# Clock_circuit.net
KiCad netlist of a schematic drawn in Altium Designer
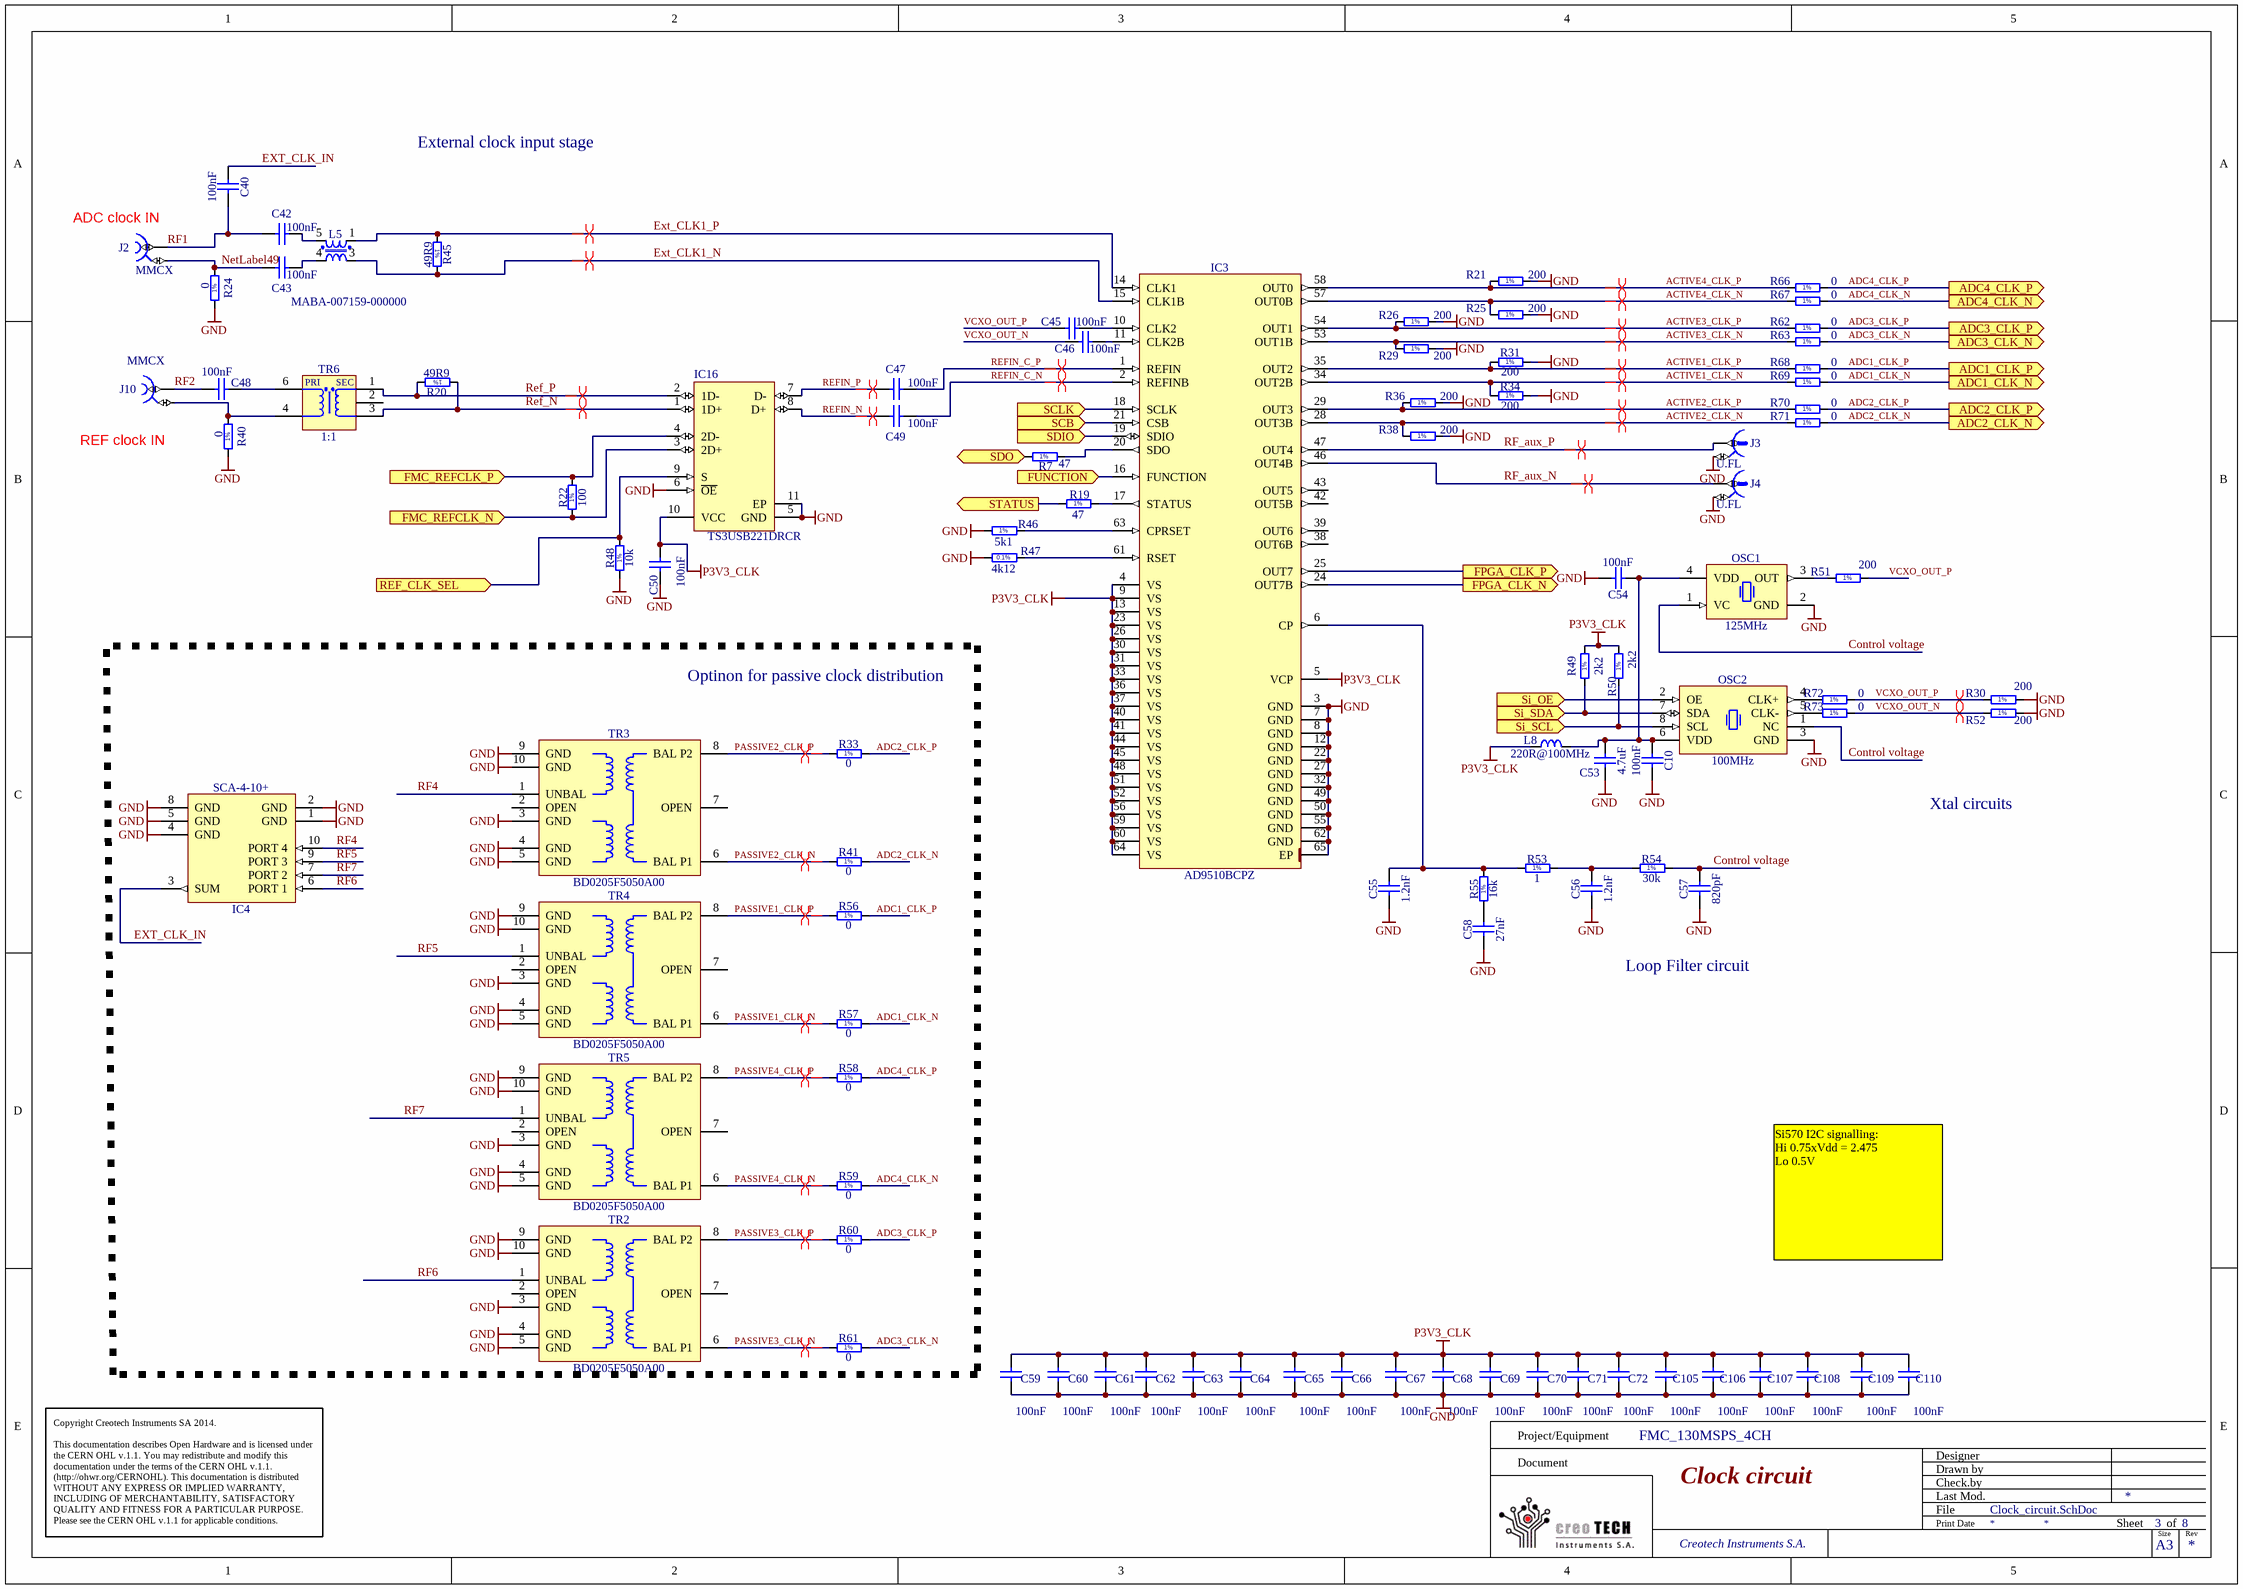
[diagram p0: Clock_circuit.SchDoc]

(export (version "E")
  (design (tool "Eeschema 10.0.6"))
  (components
    (comp (ref "C10")
      (value "100nF")
      (footprint "CAPC0603X33N")
      (description "Non-polarised capacitor")
      (fields
        (field (name "PART NUMBER") "CC0201_100NF_6.3V_10%_X5R")
        (field (name "VOLTAGE") "6.3V")
        (field (name "AUTHOR") "CERN DEM JLC")
      )
      (libsource (lib "Capacitors") (part "Capacitor - non polarized"))
    )
    (comp (ref "C40")
      (value "100nF")
      (footprint "CAPC0603X33N")
      (description "Non-polarised capacitor")
      (fields
        (field (name "PART NUMBER") "CC0201_100NF_6.3V_10%_X5R")
        (field (name "VOLTAGE") "6.3V")
        (field (name "AUTHOR") "CERN DEM JLC")
      )
      (libsource (lib "Capacitors") (part "Capacitor - non polarized"))
    )
    (comp (ref "C42")
      (value "100nF")
      (footprint "CAPC0603X33N")
      (description "Non-polarised capacitor")
      (fields
        (field (name "PART NUMBER") "CC0201_100NF_6.3V_10%_X5R")
        (field (name "VOLTAGE") "6.3V")
        (field (name "AUTHOR") "CERN DEM JLC")
      )
      (libsource (lib "Capacitors") (part "Capacitor - non polarized"))
    )
    (comp (ref "C43")
      (value "100nF")
      (footprint "CAPC0603X33N")
      (description "Non-polarised capacitor")
      (fields
        (field (name "PART NUMBER") "CC0201_100NF_6.3V_10%_X5R")
        (field (name "VOLTAGE") "6.3V")
        (field (name "AUTHOR") "CERN DEM JLC")
      )
      (libsource (lib "Capacitors") (part "Capacitor - non polarized"))
    )
    (comp (ref "C45")
      (value "100nF")
      (footprint "CAPC0603X33N")
      (description "Non-polarised capacitor")
      (fields
        (field (name "PART NUMBER") "CC0201_100NF_6.3V_10%_X5R")
        (field (name "VOLTAGE") "6.3V")
        (field (name "AUTHOR") "CERN DEM JLC")
      )
      (libsource (lib "Capacitors") (part "Capacitor - non polarized"))
    )
    (comp (ref "C46")
      (value "100nF")
      (footprint "CAPC0603X33N")
      (description "Non-polarised capacitor")
      (fields
        (field (name "PART NUMBER") "CC0201_100NF_6.3V_10%_X5R")
        (field (name "VOLTAGE") "6.3V")
        (field (name "AUTHOR") "CERN DEM JLC")
      )
      (libsource (lib "Capacitors") (part "Capacitor - non polarized"))
    )
    (comp (ref "C47")
      (value "100nF")
      (footprint "CAPC0603X33N")
      (description "Non-polarised capacitor")
      (fields
        (field (name "PART NUMBER") "CC0201_100NF_6.3V_10%_X5R")
        (field (name "VOLTAGE") "6.3V")
        (field (name "AUTHOR") "CERN DEM JLC")
      )
      (libsource (lib "Capacitors") (part "Capacitor - non polarized"))
    )
    (comp (ref "C48")
      (value "100nF")
      (footprint "CAPC0603X33N")
      (description "Non-polarised capacitor")
      (fields
        (field (name "PART NUMBER") "CC0201_100NF_6.3V_10%_X5R")
        (field (name "VOLTAGE") "6.3V")
        (field (name "AUTHOR") "CERN DEM JLC")
      )
      (libsource (lib "Capacitors") (part "Capacitor - non polarized"))
    )
    (comp (ref "C49")
      (value "100nF")
      (footprint "CAPC0603X33N")
      (description "Non-polarised capacitor")
      (fields
        (field (name "PART NUMBER") "CC0201_100NF_6.3V_10%_X5R")
        (field (name "VOLTAGE") "6.3V")
        (field (name "AUTHOR") "CERN DEM JLC")
      )
      (libsource (lib "Capacitors") (part "Capacitor - non polarized"))
    )
    (comp (ref "C50")
      (value "100nF")
      (footprint "CAPC0603X33N")
      (description "Non-polarised capacitor")
      (fields
        (field (name "PART NUMBER") "CC0201_100NF_6.3V_10%_X5R")
        (field (name "VOLTAGE") "6.3V")
        (field (name "AUTHOR") "CERN DEM JLC")
      )
      (libsource (lib "Capacitors") (part "Capacitor - non polarized"))
    )
    (comp (ref "C53")
      (value "4.7uF")
      (footprint "CAPC1608X87N")
      (description "Non-polarised capacitor")
      (fields
        (field (name "PART NUMBER") "CC0603_4.7UF_6.3V_10%_X5R")
        (field (name "VOLTAGE") "6.3V")
        (field (name "AUTHOR") "CERN DEM JLC")
      )
      (libsource (lib "Capacitors") (part "Capacitor - non polarized"))
    )
    (comp (ref "C54")
      (value "100nF")
      (footprint "CAPC0603X33N")
      (description "Non-polarised capacitor")
      (fields
        (field (name "PART NUMBER") "CC0201_100NF_6.3V_10%_X5R")
        (field (name "VOLTAGE") "6.3V")
        (field (name "AUTHOR") "CERN DEM JLC")
      )
      (libsource (lib "Capacitors") (part "Capacitor - non polarized"))
    )
    (comp (ref "C55")
      (value "1.2nF")
      (footprint "CAPC1608X87N")
      (description "Non-polarised capacitor")
      (fields
        (field (name "PART NUMBER") "CC0603_1.2NF_50V_10%_X7R")
        (field (name "VOLTAGE") "50V")
        (field (name "AUTHOR") "CERN DEM JLC")
      )
      (libsource (lib "Capacitors") (part "Capacitor - non polarized"))
    )
    (comp (ref "C56")
      (value "1.2nF")
      (footprint "CAPC1608X87N")
      (description "Non-polarised capacitor")
      (fields
        (field (name "PART NUMBER") "CC0603_1.2NF_50V_10%_X7R")
        (field (name "VOLTAGE") "50V")
        (field (name "AUTHOR") "CERN DEM JLC")
      )
      (libsource (lib "Capacitors") (part "Capacitor - non polarized"))
    )
    (comp (ref "C57")
      (value "820pF")
      (footprint "CAPC1608X87N")
      (description "Non-polarised capacitor")
      (fields
        (field (name "PART NUMBER") "CC0603_820PF_50V_10%_X7R")
        (field (name "VOLTAGE") "50V")
        (field (name "AUTHOR") "CERN DEM JLC")
      )
      (libsource (lib "Capacitors") (part "Capacitor - non polarized"))
    )
    (comp (ref "C58")
      (value "27nF")
      (footprint "CAPC1608X87N")
      (description "Non-polarised capacitor")
      (fields
        (field (name "PART NUMBER") "CC0603_27NF_25V_10%_X7R")
        (field (name "VOLTAGE") "25V")
        (field (name "AUTHOR") "CERN DEM JLC")
      )
      (libsource (lib "Capacitors") (part "Capacitor - non polarized"))
    )
    (comp (ref "C59")
      (value "100nF")
      (footprint "CAPC0603X33N")
      (description "Non-polarised capacitor")
      (fields
        (field (name "PART NUMBER") "CC0201_100NF_6.3V_10%_X5R")
        (field (name "VOLTAGE") "6.3V")
        (field (name "AUTHOR") "CERN DEM JLC")
      )
      (libsource (lib "Capacitors") (part "Capacitor - non polarized"))
    )
    (comp (ref "C60")
      (value "100nF")
      (footprint "CAPC0603X33N")
      (description "Non-polarised capacitor")
      (fields
        (field (name "PART NUMBER") "CC0201_100NF_6.3V_10%_X5R")
        (field (name "VOLTAGE") "6.3V")
        (field (name "AUTHOR") "CERN DEM JLC")
      )
      (libsource (lib "Capacitors") (part "Capacitor - non polarized"))
    )
    (comp (ref "C61")
      (value "100nF")
      (footprint "CAPC0603X33N")
      (description "Non-polarised capacitor")
      (fields
        (field (name "PART NUMBER") "CC0201_100NF_6.3V_10%_X5R")
        (field (name "VOLTAGE") "6.3V")
        (field (name "AUTHOR") "CERN DEM JLC")
      )
      (libsource (lib "Capacitors") (part "Capacitor - non polarized"))
    )
    (comp (ref "C62")
      (value "100nF")
      (footprint "CAPC0603X33N")
      (description "Non-polarised capacitor")
      (fields
        (field (name "PART NUMBER") "CC0201_100NF_6.3V_10%_X5R")
        (field (name "VOLTAGE") "6.3V")
        (field (name "AUTHOR") "CERN DEM JLC")
      )
      (libsource (lib "Capacitors") (part "Capacitor - non polarized"))
    )
    (comp (ref "C63")
      (value "100nF")
      (footprint "CAPC0603X33N")
      (description "Non-polarised capacitor")
      (fields
        (field (name "PART NUMBER") "CC0201_100NF_6.3V_10%_X5R")
        (field (name "VOLTAGE") "6.3V")
        (field (name "AUTHOR") "CERN DEM JLC")
      )
      (libsource (lib "Capacitors") (part "Capacitor - non polarized"))
    )
    (comp (ref "C64")
      (value "100nF")
      (footprint "CAPC0603X33N")
      (description "Non-polarised capacitor")
      (fields
        (field (name "PART NUMBER") "CC0201_100NF_6.3V_10%_X5R")
        (field (name "VOLTAGE") "6.3V")
        (field (name "AUTHOR") "CERN DEM JLC")
      )
      (libsource (lib "Capacitors") (part "Capacitor - non polarized"))
    )
    (comp (ref "C65")
      (value "100nF")
      (footprint "CAPC0603X33N")
      (description "Non-polarised capacitor")
      (fields
        (field (name "PART NUMBER") "CC0201_100NF_6.3V_10%_X5R")
        (field (name "VOLTAGE") "6.3V")
        (field (name "AUTHOR") "CERN DEM JLC")
      )
      (libsource (lib "Capacitors") (part "Capacitor - non polarized"))
    )
    (comp (ref "C66")
      (value "100nF")
      (footprint "CAPC0603X33N")
      (description "Non-polarised capacitor")
      (fields
        (field (name "PART NUMBER") "CC0201_100NF_6.3V_10%_X5R")
        (field (name "VOLTAGE") "6.3V")
        (field (name "AUTHOR") "CERN DEM JLC")
      )
      (libsource (lib "Capacitors") (part "Capacitor - non polarized"))
    )
    (comp (ref "C67")
      (value "100nF")
      (footprint "CAPC0603X33N")
      (description "Non-polarised capacitor")
      (fields
        (field (name "PART NUMBER") "CC0201_100NF_6.3V_10%_X5R")
        (field (name "VOLTAGE") "6.3V")
        (field (name "AUTHOR") "CERN DEM JLC")
      )
      (libsource (lib "Capacitors") (part "Capacitor - non polarized"))
    )
    (comp (ref "C68")
      (value "100nF")
      (footprint "CAPC0603X33N")
      (description "Non-polarised capacitor")
      (fields
        (field (name "PART NUMBER") "CC0201_100NF_6.3V_10%_X5R")
        (field (name "VOLTAGE") "6.3V")
        (field (name "AUTHOR") "CERN DEM JLC")
      )
      (libsource (lib "Capacitors") (part "Capacitor - non polarized"))
    )
    (comp (ref "C69")
      (value "100nF")
      (footprint "CAPC0603X33N")
      (description "Non-polarised capacitor")
      (fields
        (field (name "PART NUMBER") "CC0201_100NF_6.3V_10%_X5R")
        (field (name "VOLTAGE") "6.3V")
        (field (name "AUTHOR") "CERN DEM JLC")
      )
      (libsource (lib "Capacitors") (part "Capacitor - non polarized"))
    )
    (comp (ref "C70")
      (value "100nF")
      (footprint "CAPC0603X33N")
      (description "Non-polarised capacitor")
      (fields
        (field (name "PART NUMBER") "CC0201_100NF_6.3V_10%_X5R")
        (field (name "VOLTAGE") "6.3V")
        (field (name "AUTHOR") "CERN DEM JLC")
      )
      (libsource (lib "Capacitors") (part "Capacitor - non polarized"))
    )
    (comp (ref "C71")
      (value "100nF")
      (footprint "CAPC0603X33N")
      (description "Non-polarised capacitor")
      (fields
        (field (name "PART NUMBER") "CC0201_100NF_6.3V_10%_X5R")
        (field (name "VOLTAGE") "6.3V")
        (field (name "AUTHOR") "CERN DEM JLC")
      )
      (libsource (lib "Capacitors") (part "Capacitor - non polarized"))
    )
    (comp (ref "C72")
      (value "100nF")
      (footprint "CAPC0603X33N")
      (description "Non-polarised capacitor")
      (fields
        (field (name "PART NUMBER") "CC0201_100NF_6.3V_10%_X5R")
        (field (name "VOLTAGE") "6.3V")
        (field (name "AUTHOR") "CERN DEM JLC")
      )
      (libsource (lib "Capacitors") (part "Capacitor - non polarized"))
    )
    (comp (ref "C105")
      (value "100nF")
      (footprint "CAPC0603X33N")
      (description "Non-polarised capacitor")
      (fields
        (field (name "PART NUMBER") "CC0201_100NF_6.3V_10%_X5R")
        (field (name "VOLTAGE") "6.3V")
        (field (name "AUTHOR") "CERN DEM JLC")
      )
      (libsource (lib "Capacitors") (part "Capacitor - non polarized"))
    )
    (comp (ref "C106")
      (value "100nF")
      (footprint "CAPC0603X33N")
      (description "Non-polarised capacitor")
      (fields
        (field (name "PART NUMBER") "CC0201_100NF_6.3V_10%_X5R")
        (field (name "VOLTAGE") "6.3V")
        (field (name "AUTHOR") "CERN DEM JLC")
      )
      (libsource (lib "Capacitors") (part "Capacitor - non polarized"))
    )
    (comp (ref "C107")
      (value "100nF")
      (footprint "CAPC0603X33N")
      (description "Non-polarised capacitor")
      (fields
        (field (name "PART NUMBER") "CC0201_100NF_6.3V_10%_X5R")
        (field (name "VOLTAGE") "6.3V")
        (field (name "AUTHOR") "CERN DEM JLC")
      )
      (libsource (lib "Capacitors") (part "Capacitor - non polarized"))
    )
    (comp (ref "C108")
      (value "100nF")
      (footprint "CAPC0603X33N")
      (description "Non-polarised capacitor")
      (fields
        (field (name "PART NUMBER") "CC0201_100NF_6.3V_10%_X5R")
        (field (name "VOLTAGE") "6.3V")
        (field (name "AUTHOR") "CERN DEM JLC")
      )
      (libsource (lib "Capacitors") (part "Capacitor - non polarized"))
    )
    (comp (ref "C109")
      (value "100nF")
      (footprint "CAPC0603X33N")
      (description "Non-polarised capacitor")
      (fields
        (field (name "PART NUMBER") "CC0201_100NF_6.3V_10%_X5R")
        (field (name "VOLTAGE") "6.3V")
        (field (name "AUTHOR") "CERN DEM JLC")
      )
      (libsource (lib "Capacitors") (part "Capacitor - non polarized"))
    )
    (comp (ref "C110")
      (value "100nF")
      (footprint "CAPC0603X33N")
      (description "Non-polarised capacitor")
      (fields
        (field (name "PART NUMBER") "CC0201_100NF_6.3V_10%_X5R")
        (field (name "VOLTAGE") "6.3V")
        (field (name "AUTHOR") "CERN DEM JLC")
      )
      (libsource (lib "Capacitors") (part "Capacitor - non polarized"))
    )
    (comp (ref "IC3")
      (value "AD9510BCPZ")
      (footprint "QFN50P900X900X100-65N-S485")
      (description "1.2 GHz Clock Distribution IC, PLL Core, Dividers, Delay Adjust, Eight Outputs")
      (fields (field (name "MANUFACTURER") "ANALOG DEVICES") (field (name "AUTHOR") "CERN DEM JLC"))
      (libsource (lib "ICs And Semiconductors") (part "AD9510"))
    )
    (comp (ref "IC4")
      (value "SCA-4-10+")
      (footprint "MINI-CIRCUITS_DZ943")
      (description "4 Way-0° 50 OHM 5 to 1000 MHz Power Splitter/Combiner")
      (fields (field (name "MANUFACTURER") "MINI-CIRCUITS") (field (name "AUTHOR") "CERN DEM JLC"))
      (libsource (lib "ICs And Semiconductors") (part "SCA-4-10+"))
    )
    (comp (ref "IC16")
      (value "TS3USB221DRCR")
      (footprint "DRC10-2400X1650TP")
      (fields (field (name "MANUFACTURER") "Texas Instruments"))
      (libsource (lib "fmclib") (part "TS3USB221DRCR"))
    )
    (comp (ref "J2")
      (value "Coax_1Female_1Shield")
      (footprint "HUBER-SUHNER_85_MMCX-50-0-1/111 OH")
      (fields
        (field (name "PART NUMBER") "HUBER-SUHNER_85_MMCX-50-0-1/111 OH")
        (field (name "FAMILY") "MMCX")
        (field (name "MANUFACTURER") "HUBER+SUHNER")
        (field (name "MANUFACTURER PART NUMBER") "85_MMCX-50-0-1/111 OH")
        (field (name "AUTHOR") "CERN DEM JLC")
      )
      (libsource (lib "Connectors") (part "Coax_1Female_1Shield"))
    )
    (comp (ref "J3")
      (value "U.FL")
      (footprint "HIROSE_U.FL-R-SMT-1(10)")
      (fields
        (field (name "PART NUMBER") "HIROSE_U.FL-R-SMT-1(10)")
        (field (name "MANUFACTURER") "HIROSE (HRS)")
        (field (name "MANUFACTURER PART NUMBER") "U.FL-R-SMT-1(10)")
        (field (name "AUTHOR") "CERN DEM JLC")
      )
      (libsource (lib "Connectors") (part "Coax_1Male_1Shield"))
    )
    (comp (ref "J4")
      (value "U.FL")
      (footprint "HIROSE_U.FL-R-SMT-1(10)")
      (fields
        (field (name "PART NUMBER") "HIROSE_U.FL-R-SMT-1(10)")
        (field (name "MANUFACTURER") "HIROSE (HRS)")
        (field (name "MANUFACTURER PART NUMBER") "U.FL-R-SMT-1(10)")
        (field (name "AUTHOR") "CERN DEM JLC")
      )
      (libsource (lib "Connectors") (part "Coax_1Male_1Shield"))
    )
    (comp (ref "J10")
      (value "Coax_1Female_1Shield")
      (footprint "HUBER-SUHNER_85_MMCX-50-0-1/111 OH")
      (fields
        (field (name "PART NUMBER") "HUBER-SUHNER_85_MMCX-50-0-1/111 OH")
        (field (name "FAMILY") "MMCX")
        (field (name "MANUFACTURER") "HUBER+SUHNER")
        (field (name "MANUFACTURER PART NUMBER") "85_MMCX-50-0-1/111 OH")
        (field (name "AUTHOR") "CERN DEM JLC")
      )
      (libsource (lib "Connectors") (part "Coax_1Female_1Shield"))
    )
    (comp (ref "L5")
      (value "MABA-007159-000000")
      (footprint "XFMR_MA-COM_SM-22 (H260)")
      (description "MA-COM E-Serie RF 1:1 Transmission Line Ttransformer 4.5-3000MHz")
      (fields
        (field (name "PART NUMBER") "XFMR_MA-COM_MABA-007159-000000")
        (field (name "MANUFACTURER") "MA-COM TECHNOLOGY")
        (field (name "AUTHOR") "CERN DEM JLC")
      )
      (libsource (lib "Inductors & Transformers") (part "XFMR_MA-COM_MABA-007159-000000"))
    )
    (comp (ref "L8")
      (value "220R@100MHz")
      (footprint "INDC1005X55N")
      (description "Inductor")
      (fields
        (field (name "PART NUMBER") "IND0402_MURATA_BLM15HB221SN1")
        (field (name "POWER") "250mA")
        (field (name "AUTHOR") "CERN DEM JLC")
      )
      (libsource (lib "Inductors & Transformers") (part "Inductor"))
    )
    (comp (ref "OSC1")
      (value "125MHz")
      (footprint "OSC_CRYSTEK_CVHD-950")
      (description "Oscillator 4 pins 1=VC 2=GND 3=OUT 4=VDD")
      (fields
        (field (name "PART NUMBER") "OSC_125MHZ_CRYSTEK_CVHD-950-100.000")
        (field (name "MANUFACTURER") "CRYSTEK CRYSTAL")
        (field (name "AUTHOR") "CERN DEM JLC")
      )
      (libsource (lib "ICs And Semiconductors") (part "Oscillator 1VC 2GND 3OUT 4VDD"))
    )
    (comp (ref "OSC2")
      (value "100MHz")
      (footprint "OSC_SILICON-LAB_SI570")
      (description "Any-Rate I2C Programmable XO Oscillator Si570 Serie")
      (fields
        (field (name "PART NUMBER") "OSC_10-280MHZ_SILICON-LAB_Si570BBC000121DG")
        (field (name "MANUFACTURER") "SILICON LABS")
        (field (name "AUTHOR") "CERN DEM JLC")
      )
      (libsource (lib "ICs And Semiconductors") (part "Oscillator SILICON-LAB_Si570"))
    )
    (comp (ref "R7")
      (value "47")
      (footprint "RESC1005X40N")
      (description "Resistor - 1%")
      (fields
        (field (name "PART NUMBER") "R0402_47R_1%_0.0625W_100PPM")
        (field (name "POWER") "0.0625W")
        (field (name "AUTHOR") "CERN DEM JLC")
      )
      (libsource (lib "Resistors") (part "Resistor - 1%"))
    )
    (comp (ref "R19")
      (value "47")
      (footprint "RESC1005X40N")
      (description "Resistor - 1%")
      (fields
        (field (name "PART NUMBER") "R0402_47R_1%_0.0625W_100PPM")
        (field (name "POWER") "0.0625W")
        (field (name "AUTHOR") "CERN DEM JLC")
      )
      (libsource (lib "Resistors") (part "Resistor - 1%"))
    )
    (comp (ref "R20")
      (value "49R9")
      (footprint "RESC1005X40N")
      (description "Resistor - 1%")
      (fields
        (field (name "PART NUMBER") "R0402_49R9_1%_0.0625W_100PPM")
        (field (name "POWER") "0.0625W")
        (field (name "AUTHOR") "CERN DEM JLC")
      )
      (libsource (lib "Resistors") (part "Resistor - 1%"))
    )
    (comp (ref "R21")
      (value "200")
      (footprint "RESC1005X40N")
      (description "Resistor - 1%")
      (fields
        (field (name "PART NUMBER") "R0402_200R_1%_0.0625W_100PPM")
        (field (name "POWER") "0.0625W")
        (field (name "AUTHOR") "CERN DEM JLC")
      )
      (libsource (lib "Resistors") (part "Resistor - 1%"))
    )
    (comp (ref "R22")
      (value "100")
      (footprint "RESC1005X40N")
      (description "Resistor - 1%")
      (fields
        (field (name "PART NUMBER") "R0402_100R_1%_0.0625W_100PPM")
        (field (name "POWER") "0.0625W")
        (field (name "AUTHOR") "CERN DEM JLC")
      )
      (libsource (lib "Resistors") (part "Resistor - 1%"))
    )
    (comp (ref "R24")
      (value "0")
      (footprint "RESC1005X40N")
      (description "Resistor - 1%")
      (fields
        (field (name "PART NUMBER") "R0402_0R_JUMPER")
        (field (name "MANUFACTURER") "GENERIC")
        (field (name "AUTHOR") "CERN DEM JLC")
      )
      (libsource (lib "Resistors") (part "Resistor - 1%"))
    )
    (comp (ref "R25")
      (value "200")
      (footprint "RESC1005X40N")
      (description "Resistor - 1%")
      (fields
        (field (name "PART NUMBER") "R0402_200R_1%_0.0625W_100PPM")
        (field (name "POWER") "0.0625W")
        (field (name "AUTHOR") "CERN DEM JLC")
      )
      (libsource (lib "Resistors") (part "Resistor - 1%"))
    )
    (comp (ref "R26")
      (value "200")
      (footprint "RESC1005X40N")
      (description "Resistor - 1%")
      (fields
        (field (name "PART NUMBER") "R0402_200R_1%_0.0625W_100PPM")
        (field (name "POWER") "0.0625W")
        (field (name "AUTHOR") "CERN DEM JLC")
      )
      (libsource (lib "Resistors") (part "Resistor - 1%"))
    )
    (comp (ref "R29")
      (value "200")
      (footprint "RESC1005X40N")
      (description "Resistor - 1%")
      (fields
        (field (name "PART NUMBER") "R0402_200R_1%_0.0625W_100PPM")
        (field (name "POWER") "0.0625W")
        (field (name "AUTHOR") "CERN DEM JLC")
      )
      (libsource (lib "Resistors") (part "Resistor - 1%"))
    )
    (comp (ref "R30")
      (value "200")
      (footprint "RESC1005X40N")
      (description "Resistor - 1%")
      (fields
        (field (name "PART NUMBER") "R0402_200R_1%_0.0625W_100PPM")
        (field (name "POWER") "0.0625W")
        (field (name "AUTHOR") "CERN DEM JLC")
      )
      (libsource (lib "Resistors") (part "Resistor - 1%"))
    )
    (comp (ref "R31")
      (value "200")
      (footprint "RESC1005X40N")
      (description "Resistor - 1%")
      (fields
        (field (name "PART NUMBER") "R0402_200R_1%_0.0625W_100PPM")
        (field (name "POWER") "0.0625W")
        (field (name "AUTHOR") "CERN DEM JLC")
      )
      (libsource (lib "Resistors") (part "Resistor - 1%"))
    )
    (comp (ref "R33")
      (value "0")
      (footprint "RESC1005X40N")
      (description "Resistor - 1%")
      (fields
        (field (name "PART NUMBER") "R0402_0R_JUMPER")
        (field (name "MANUFACTURER") "GENERIC")
        (field (name "AUTHOR") "CERN DEM JLC")
      )
      (libsource (lib "Resistors") (part "Resistor - 1%"))
    )
    (comp (ref "R34")
      (value "200")
      (footprint "RESC1005X40N")
      (description "Resistor - 1%")
      (fields
        (field (name "PART NUMBER") "R0402_200R_1%_0.0625W_100PPM")
        (field (name "POWER") "0.0625W")
        (field (name "AUTHOR") "CERN DEM JLC")
      )
      (libsource (lib "Resistors") (part "Resistor - 1%"))
    )
    (comp (ref "R36")
      (value "200")
      (footprint "RESC1005X40N")
      (description "Resistor - 1%")
      (fields
        (field (name "PART NUMBER") "R0402_200R_1%_0.0625W_100PPM")
        (field (name "POWER") "0.0625W")
        (field (name "AUTHOR") "CERN DEM JLC")
      )
      (libsource (lib "Resistors") (part "Resistor - 1%"))
    )
    (comp (ref "R38")
      (value "200")
      (footprint "RESC1005X40N")
      (description "Resistor - 1%")
      (fields
        (field (name "PART NUMBER") "R0402_200R_1%_0.0625W_100PPM")
        (field (name "POWER") "0.0625W")
        (field (name "AUTHOR") "CERN DEM JLC")
      )
      (libsource (lib "Resistors") (part "Resistor - 1%"))
    )
    (comp (ref "R40")
      (value "0")
      (footprint "RESC1005X40N")
      (description "Resistor - 1%")
      (fields
        (field (name "PART NUMBER") "R0402_0R_JUMPER")
        (field (name "MANUFACTURER") "GENERIC")
        (field (name "AUTHOR") "CERN DEM JLC")
      )
      (libsource (lib "Resistors") (part "Resistor - 1%"))
    )
    (comp (ref "R41")
      (value "0")
      (footprint "RESC1005X40N")
      (description "Resistor - 1%")
      (fields
        (field (name "PART NUMBER") "R0402_0R_JUMPER")
        (field (name "MANUFACTURER") "GENERIC")
        (field (name "AUTHOR") "CERN DEM JLC")
      )
      (libsource (lib "Resistors") (part "Resistor - 1%"))
    )
    (comp (ref "R45")
      (value "49R9")
      (footprint "RESC1005X40N")
      (description "Resistor - 1%")
      (fields
        (field (name "PART NUMBER") "R0402_49R9_1%_0.0625W_100PPM")
        (field (name "POWER") "0.0625W")
        (field (name "AUTHOR") "CERN DEM JLC")
      )
      (libsource (lib "Resistors") (part "Resistor - 1%"))
    )
    (comp (ref "R46")
      (value "5k1")
      (footprint "RESC1005X40N")
      (description "Resistor - 1%")
      (fields
        (field (name "PART NUMBER") "R0402_5K1_1%_0.0625W_100PPM")
        (field (name "POWER") "0.0625W")
        (field (name "AUTHOR") "CERN DEM JLC")
      )
      (libsource (lib "Resistors") (part "Resistor - 1%"))
    )
    (comp (ref "R47")
      (value "4k12")
      (footprint "RESC1608X55N")
      (description "Resistor - 0.1%")
      (fields
        (field (name "PART NUMBER") "R0603_4K12_0.1%_0.063W_10PPM")
        (field (name "POWER") "0.063W")
        (field (name "AUTHOR") "CERN DEM JLC")
      )
      (libsource (lib "Resistors") (part "Resistor - 0.1%"))
    )
    (comp (ref "R48")
      (value "10k")
      (footprint "RESC1005X40N")
      (description "Resistor - 1%")
      (fields
        (field (name "PART NUMBER") "R0402_10K_1%_0.0625W_100PPM")
        (field (name "POWER") "0.0625W")
        (field (name "AUTHOR") "CERN DEM JLC")
      )
      (libsource (lib "Resistors") (part "Resistor - 1%"))
    )
    (comp (ref "R49")
      (value "2k2")
      (footprint "RESC1005X40N")
      (description "Resistor - 1%")
      (fields
        (field (name "PART NUMBER") "R0402_2K2_1%_0.0625W_100PPM")
        (field (name "POWER") "0.0625W")
        (field (name "AUTHOR") "CERN DEM JLC")
      )
      (libsource (lib "Resistors") (part "Resistor - 1%"))
    )
    (comp (ref "R50")
      (value "2k2")
      (footprint "RESC1005X40N")
      (description "Resistor - 1%")
      (fields
        (field (name "PART NUMBER") "R0402_2K2_1%_0.0625W_100PPM")
        (field (name "POWER") "0.0625W")
        (field (name "AUTHOR") "CERN DEM JLC")
      )
      (libsource (lib "Resistors") (part "Resistor - 1%"))
    )
    (comp (ref "R51")
      (value "200")
      (footprint "RESC1005X40N")
      (description "Resistor - 1%")
      (fields
        (field (name "PART NUMBER") "R0402_200R_1%_0.0625W_100PPM")
        (field (name "POWER") "0.0625W")
        (field (name "AUTHOR") "CERN DEM JLC")
      )
      (libsource (lib "Resistors") (part "Resistor - 1%"))
    )
    (comp (ref "R52")
      (value "200")
      (footprint "RESC1005X40N")
      (description "Resistor - 1%")
      (fields
        (field (name "PART NUMBER") "R0402_200R_1%_0.0625W_100PPM")
        (field (name "POWER") "0.0625W")
        (field (name "AUTHOR") "CERN DEM JLC")
      )
      (libsource (lib "Resistors") (part "Resistor - 1%"))
    )
    (comp (ref "R53")
      (value "1")
      (footprint "RESC1005X40N")
      (description "Resistor - 1%")
      (fields
        (field (name "PART NUMBER") "R0402_1R_1%_0.0625W_200PPM")
        (field (name "POWER") "0.0625W")
        (field (name "AUTHOR") "CERN DEM JLC")
      )
      (libsource (lib "Resistors") (part "Resistor - 1%"))
    )
    (comp (ref "R54")
      (value "30k")
      (footprint "RESC1005X40N")
      (description "Resistor - 1%")
      (fields
        (field (name "PART NUMBER") "R0402_30K_1%_0.0625W_100PPM")
        (field (name "POWER") "0.0625W")
        (field (name "AUTHOR") "CERN DEM JLC")
      )
      (libsource (lib "Resistors") (part "Resistor - 1%"))
    )
    (comp (ref "R55")
      (value "16k")
      (footprint "RESC1005X40N")
      (description "Resistor - 1%")
      (fields
        (field (name "PART NUMBER") "R0402_16K_1%_0.0625W_100PPM")
        (field (name "POWER") "0.0625W")
        (field (name "AUTHOR") "CERN DEM JLC")
      )
      (libsource (lib "Resistors") (part "Resistor - 1%"))
    )
    (comp (ref "R56")
      (value "0")
      (footprint "RESC1005X40N")
      (description "Resistor - 1%")
      (fields
        (field (name "PART NUMBER") "R0402_0R_JUMPER")
        (field (name "MANUFACTURER") "GENERIC")
        (field (name "AUTHOR") "CERN DEM JLC")
      )
      (libsource (lib "Resistors") (part "Resistor - 1%"))
    )
    (comp (ref "R57")
      (value "0")
      (footprint "RESC1005X40N")
      (description "Resistor - 1%")
      (fields
        (field (name "PART NUMBER") "R0402_0R_JUMPER")
        (field (name "MANUFACTURER") "GENERIC")
        (field (name "AUTHOR") "CERN DEM JLC")
      )
      (libsource (lib "Resistors") (part "Resistor - 1%"))
    )
    (comp (ref "R58")
      (value "0")
      (footprint "RESC1005X40N")
      (description "Resistor - 1%")
      (fields
        (field (name "PART NUMBER") "R0402_0R_JUMPER")
        (field (name "MANUFACTURER") "GENERIC")
        (field (name "AUTHOR") "CERN DEM JLC")
      )
      (libsource (lib "Resistors") (part "Resistor - 1%"))
    )
    (comp (ref "R59")
      (value "0")
      (footprint "RESC1005X40N")
      (description "Resistor - 1%")
      (fields
        (field (name "PART NUMBER") "R0402_0R_JUMPER")
        (field (name "MANUFACTURER") "GENERIC")
        (field (name "AUTHOR") "CERN DEM JLC")
      )
      (libsource (lib "Resistors") (part "Resistor - 1%"))
    )
    (comp (ref "R60")
      (value "0")
      (footprint "RESC1005X40N")
      (description "Resistor - 1%")
      (fields
        (field (name "PART NUMBER") "R0402_0R_JUMPER")
        (field (name "MANUFACTURER") "GENERIC")
        (field (name "AUTHOR") "CERN DEM JLC")
      )
      (libsource (lib "Resistors") (part "Resistor - 1%"))
    )
    (comp (ref "R61")
      (value "0")
      (footprint "RESC1005X40N")
      (description "Resistor - 1%")
      (fields
        (field (name "PART NUMBER") "R0402_0R_JUMPER")
        (field (name "MANUFACTURER") "GENERIC")
        (field (name "AUTHOR") "CERN DEM JLC")
      )
      (libsource (lib "Resistors") (part "Resistor - 1%"))
    )
    (comp (ref "R62")
      (value "0")
      (footprint "RESC1005X40N")
      (description "Resistor - 1%")
      (fields
        (field (name "PART NUMBER") "R0402_0R_JUMPER")
        (field (name "MANUFACTURER") "GENERIC")
        (field (name "AUTHOR") "CERN DEM JLC")
      )
      (libsource (lib "Resistors") (part "Resistor - 1%"))
    )
    (comp (ref "R63")
      (value "0")
      (footprint "RESC1005X40N")
      (description "Resistor - 1%")
      (fields
        (field (name "PART NUMBER") "R0402_0R_JUMPER")
        (field (name "MANUFACTURER") "GENERIC")
        (field (name "AUTHOR") "CERN DEM JLC")
      )
      (libsource (lib "Resistors") (part "Resistor - 1%"))
    )
    (comp (ref "R66")
      (value "0")
      (footprint "RESC1005X40N")
      (description "Resistor - 1%")
      (fields
        (field (name "PART NUMBER") "R0402_0R_JUMPER")
        (field (name "MANUFACTURER") "GENERIC")
        (field (name "AUTHOR") "CERN DEM JLC")
      )
      (libsource (lib "Resistors") (part "Resistor - 1%"))
    )
    (comp (ref "R67")
      (value "0")
      (footprint "RESC1005X40N")
      (description "Resistor - 1%")
      (fields
        (field (name "PART NUMBER") "R0402_0R_JUMPER")
        (field (name "MANUFACTURER") "GENERIC")
        (field (name "AUTHOR") "CERN DEM JLC")
      )
      (libsource (lib "Resistors") (part "Resistor - 1%"))
    )
    (comp (ref "R68")
      (value "0")
      (footprint "RESC1005X40N")
      (description "Resistor - 1%")
      (fields
        (field (name "PART NUMBER") "R0402_0R_JUMPER")
        (field (name "MANUFACTURER") "GENERIC")
        (field (name "AUTHOR") "CERN DEM JLC")
      )
      (libsource (lib "Resistors") (part "Resistor - 1%"))
    )
    (comp (ref "R69")
      (value "0")
      (footprint "RESC1005X40N")
      (description "Resistor - 1%")
      (fields
        (field (name "PART NUMBER") "R0402_0R_JUMPER")
        (field (name "MANUFACTURER") "GENERIC")
        (field (name "AUTHOR") "CERN DEM JLC")
      )
      (libsource (lib "Resistors") (part "Resistor - 1%"))
    )
    (comp (ref "R70")
      (value "0")
      (footprint "RESC1005X40N")
      (description "Resistor - 1%")
      (fields
        (field (name "PART NUMBER") "R0402_0R_JUMPER")
        (field (name "MANUFACTURER") "GENERIC")
        (field (name "AUTHOR") "CERN DEM JLC")
      )
      (libsource (lib "Resistors") (part "Resistor - 1%"))
    )
    (comp (ref "R71")
      (value "0")
      (footprint "RESC1005X40N")
      (description "Resistor - 1%")
      (fields
        (field (name "PART NUMBER") "R0402_0R_JUMPER")
        (field (name "MANUFACTURER") "GENERIC")
        (field (name "AUTHOR") "CERN DEM JLC")
      )
      (libsource (lib "Resistors") (part "Resistor - 1%"))
    )
    (comp (ref "R72")
      (value "0")
      (footprint "RESC1005X40N")
      (description "Resistor - 1%")
      (fields
        (field (name "PART NUMBER") "R0402_0R_JUMPER")
        (field (name "MANUFACTURER") "GENERIC")
        (field (name "AUTHOR") "CERN DEM JLC")
      )
      (libsource (lib "Resistors") (part "Resistor - 1%"))
    )
    (comp (ref "R73")
      (value "0")
      (footprint "RESC1005X40N")
      (description "Resistor - 1%")
      (fields
        (field (name "PART NUMBER") "R0402_0R_JUMPER")
        (field (name "MANUFACTURER") "GENERIC")
        (field (name "AUTHOR") "CERN DEM JLC")
      )
      (libsource (lib "Resistors") (part "Resistor - 1%"))
    )
    (comp (ref "TR2")
      (value "BD0205F5050A00")
      (footprint "XFMR_ANAREN_BD0205F5050A00")
      (description "70MHz - 1000MHz Ultra Low Profile Sub-Miniature Balanced to Unbalanced Transformer")
      (fields
        (field (name "PART NUMBER") "XFMR_ANAREN_BD0205F5050A00")
        (field (name "MANUFACTURER") "ANAREN")
        (field (name "AUTHOR") "CERN DEM JLC")
      )
      (libsource (lib "Inductors & Transformers") (part "XFMR_ANAREN_BD0205F5050A00"))
    )
    (comp (ref "TR3")
      (value "BD0205F5050A00")
      (footprint "XFMR_ANAREN_BD0205F5050A00")
      (description "70MHz - 1000MHz Ultra Low Profile Sub-Miniature Balanced to Unbalanced Transformer")
      (fields
        (field (name "PART NUMBER") "XFMR_ANAREN_BD0205F5050A00")
        (field (name "MANUFACTURER") "ANAREN")
        (field (name "AUTHOR") "CERN DEM JLC")
      )
      (libsource (lib "Inductors & Transformers") (part "XFMR_ANAREN_BD0205F5050A00"))
    )
    (comp (ref "TR4")
      (value "BD0205F5050A00")
      (footprint "XFMR_ANAREN_BD0205F5050A00")
      (description "70MHz - 1000MHz Ultra Low Profile Sub-Miniature Balanced to Unbalanced Transformer")
      (fields
        (field (name "PART NUMBER") "XFMR_ANAREN_BD0205F5050A00")
        (field (name "MANUFACTURER") "ANAREN")
        (field (name "AUTHOR") "CERN DEM JLC")
      )
      (libsource (lib "Inductors & Transformers") (part "XFMR_ANAREN_BD0205F5050A00"))
    )
    (comp (ref "TR5")
      (value "BD0205F5050A00")
      (footprint "XFMR_ANAREN_BD0205F5050A00")
      (description "70MHz - 1000MHz Ultra Low Profile Sub-Miniature Balanced to Unbalanced Transformer")
      (fields
        (field (name "PART NUMBER") "XFMR_ANAREN_BD0205F5050A00")
        (field (name "MANUFACTURER") "ANAREN")
        (field (name "AUTHOR") "CERN DEM JLC")
      )
      (libsource (lib "Inductors & Transformers") (part "XFMR_ANAREN_BD0205F5050A00"))
    )
    (comp (ref "TR6")
      (value "1:1")
      (footprint "XFMR_MINI-CIRCUITS_AT224-1")
      (description "50 Ohm  0.4 To 500MHz RF Transformers")
      (fields
        (field (name "PART NUMBER") "XFMR_MINI-CIRCUITS_TC1-1T+")
        (field (name "MANUFACTURER") "MINI-CIRCUITS")
        (field (name "AUTHOR") "CERN DEM JLC")
      )
      (libsource (lib "Inductors & Transformers") (part "XFMR_MINI-CIRCUITS_TC1-1+"))
    )
  )
  (nets
    (net (code "1") (name "/ACTIVE1_CLK_N") (class "Default")
      (node (ref "IC3") (pin "34") (pinfunction "OUT2B_34") (pintype "output"))
      (node (ref "R34") (pin "1") (pinfunction "1_1") (pintype "passive"))
      (node (ref "R69") (pin "1") (pinfunction "1_1") (pintype "passive"))
    )
    (net (code "2") (name "/ACTIVE1_CLK_P") (class "Default")
      (node (ref "IC3") (pin "35") (pinfunction "OUT2_35") (pintype "output"))
      (node (ref "R31") (pin "1") (pinfunction "1_1") (pintype "passive"))
      (node (ref "R68") (pin "1") (pinfunction "1_1") (pintype "passive"))
    )
    (net (code "3") (name "/ACTIVE2_CLK_N") (class "Default")
      (node (ref "IC3") (pin "28") (pinfunction "OUT3B_28") (pintype "output"))
      (node (ref "R38") (pin "1") (pinfunction "1_1") (pintype "passive"))
      (node (ref "R71") (pin "1") (pinfunction "1_1") (pintype "passive"))
    )
    (net (code "4") (name "/ACTIVE2_CLK_P") (class "Default")
      (node (ref "IC3") (pin "29") (pinfunction "OUT3_29") (pintype "output"))
      (node (ref "R36") (pin "1") (pinfunction "1_1") (pintype "passive"))
      (node (ref "R70") (pin "1") (pinfunction "1_1") (pintype "passive"))
    )
    (net (code "5") (name "/ACTIVE3_CLK_N") (class "Default")
      (node (ref "IC3") (pin "53") (pinfunction "OUT1B_53") (pintype "output"))
      (node (ref "R29") (pin "1") (pinfunction "1_1") (pintype "passive"))
      (node (ref "R63") (pin "1") (pinfunction "1_1") (pintype "passive"))
    )
    (net (code "6") (name "/ACTIVE3_CLK_P") (class "Default")
      (node (ref "IC3") (pin "54") (pinfunction "OUT1_54") (pintype "output"))
      (node (ref "R26") (pin "1") (pinfunction "1_1") (pintype "passive"))
      (node (ref "R62") (pin "1") (pinfunction "1_1") (pintype "passive"))
    )
    (net (code "7") (name "/ACTIVE4_CLK_N") (class "Default")
      (node (ref "IC3") (pin "57") (pinfunction "OUT0B_57") (pintype "output"))
      (node (ref "R25") (pin "1") (pinfunction "1_1") (pintype "passive"))
      (node (ref "R67") (pin "1") (pinfunction "1_1") (pintype "passive"))
    )
    (net (code "8") (name "/ACTIVE4_CLK_P") (class "Default")
      (node (ref "IC3") (pin "58") (pinfunction "OUT0_58") (pintype "output"))
      (node (ref "R21") (pin "1") (pinfunction "1_1") (pintype "passive"))
      (node (ref "R66") (pin "1") (pinfunction "1_1") (pintype "passive"))
    )
    (net (code "9") (name "/ADC1_CLK_N") (class "Default")
      (node (ref "R57") (pin "2") (pinfunction "2_2") (pintype "passive"))
      (node (ref "R69") (pin "2") (pinfunction "2_2") (pintype "passive"))
    )
    (net (code "10") (name "/ADC1_CLK_P") (class "Default")
      (node (ref "R56") (pin "2") (pinfunction "2_2") (pintype "passive"))
      (node (ref "R68") (pin "2") (pinfunction "2_2") (pintype "passive"))
    )
    (net (code "11") (name "/ADC2_CLK_N") (class "Default")
      (node (ref "R41") (pin "2") (pinfunction "2_2") (pintype "passive"))
      (node (ref "R71") (pin "2") (pinfunction "2_2") (pintype "passive"))
    )
    (net (code "12") (name "/ADC2_CLK_P") (class "Default")
      (node (ref "R33") (pin "2") (pinfunction "2_2") (pintype "passive"))
      (node (ref "R70") (pin "2") (pinfunction "2_2") (pintype "passive"))
    )
    (net (code "13") (name "/ADC3_CLK_N") (class "Default")
      (node (ref "R61") (pin "2") (pinfunction "2_2") (pintype "passive"))
      (node (ref "R63") (pin "2") (pinfunction "2_2") (pintype "passive"))
    )
    (net (code "14") (name "/ADC3_CLK_P") (class "Default")
      (node (ref "R60") (pin "2") (pinfunction "2_2") (pintype "passive"))
      (node (ref "R62") (pin "2") (pinfunction "2_2") (pintype "passive"))
    )
    (net (code "15") (name "/ADC4_CLK_N") (class "Default")
      (node (ref "R59") (pin "2") (pinfunction "2_2") (pintype "passive"))
      (node (ref "R67") (pin "2") (pinfunction "2_2") (pintype "passive"))
    )
    (net (code "16") (name "/ADC4_CLK_P") (class "Default")
      (node (ref "R58") (pin "2") (pinfunction "2_2") (pintype "passive"))
      (node (ref "R66") (pin "2") (pinfunction "2_2") (pintype "passive"))
    )
    (net (code "17") (name "/Control voltage") (class "Default")
      (node (ref "C57") (pin "2") (pinfunction "2_2") (pintype "passive"))
      (node (ref "OSC1") (pin "1") (pinfunction "VC_1") (pintype "input"))
      (node (ref "OSC2") (pin "1") (pinfunction "NC_1") (pintype "passive"))
      (node (ref "R54") (pin "2") (pinfunction "2_2") (pintype "passive"))
    )
    (net (code "18") (name "/EXT_CLK_IN") (class "Default")
      (node (ref "C40") (pin "1") (pinfunction "1_1") (pintype "passive"))
      (node (ref "IC4") (pin "3") (pinfunction "SUM_3") (pintype "output"))
    )
    (net (code "19") (name "/Ext_CLK1_N") (class "Default")
      (node (ref "IC3") (pin "15") (pinfunction "CLK1B_15") (pintype "input"))
      (node (ref "L5") (pin "3") (pinfunction "3_3") (pintype "passive"))
      (node (ref "R45") (pin "2") (pinfunction "2_2") (pintype "passive"))
    )
    (net (code "20") (name "/Ext_CLK1_P") (class "Default")
      (node (ref "IC3") (pin "14") (pinfunction "CLK1_14") (pintype "input"))
      (node (ref "L5") (pin "1") (pinfunction "1_1") (pintype "passive"))
      (node (ref "R45") (pin "1") (pinfunction "1_1") (pintype "passive"))
    )
    (net (code "21") (name "/FMC_REFCLK_N") (class "Default")
      (node (ref "IC16") (pin "3") (pinfunction "2D+_3") (pintype "bidirectional"))
      (node (ref "R22") (pin "1") (pinfunction "1_1") (pintype "passive"))
    )
    (net (code "22") (name "/FMC_REFCLK_P") (class "Default")
      (node (ref "IC16") (pin "4") (pinfunction "2D-_4") (pintype "bidirectional"))
      (node (ref "R22") (pin "2") (pinfunction "2_2") (pintype "passive"))
    )
    (net (code "23") (name "/FPGA_CLK_N") (class "Default")
      (node (ref "IC3") (pin "24") (pinfunction "OUT7B_24") (pintype "output"))
    )
    (net (code "24") (name "/FPGA_CLK_P") (class "Default")
      (node (ref "IC3") (pin "25") (pinfunction "OUT7_25") (pintype "output"))
    )
    (net (code "25") (name "/FUNCTION") (class "Default")
      (node (ref "IC3") (pin "16") (pinfunction "FUNCTION_16") (pintype "input"))
    )
    (net (code "26") (name "/NetLabel49") (class "Default")
      (node (ref "C43") (pin "2") (pinfunction "2_2") (pintype "passive"))
      (node (ref "J2") (pin "2") (pinfunction "2_2") (pintype "bidirectional"))
      (node (ref "R24") (pin "2") (pinfunction "2_2") (pintype "passive"))
    )
    (net (code "27") (name "/PASSIVE1_CLK_N") (class "Default")
      (node (ref "R57") (pin "1") (pinfunction "1_1") (pintype "passive"))
      (node (ref "TR4") (pin "6") (pinfunction "BAL_P1_6") (pintype "passive"))
    )
    (net (code "28") (name "/PASSIVE1_CLK_P") (class "Default")
      (node (ref "R56") (pin "1") (pinfunction "1_1") (pintype "passive"))
      (node (ref "TR4") (pin "8") (pinfunction "BAL_P2_8") (pintype "passive"))
    )
    (net (code "29") (name "/PASSIVE2_CLK_N") (class "Default")
      (node (ref "R41") (pin "1") (pinfunction "1_1") (pintype "passive"))
      (node (ref "TR3") (pin "6") (pinfunction "BAL_P1_6") (pintype "passive"))
    )
    (net (code "30") (name "/PASSIVE2_CLK_P") (class "Default")
      (node (ref "R33") (pin "1") (pinfunction "1_1") (pintype "passive"))
      (node (ref "TR3") (pin "8") (pinfunction "BAL_P2_8") (pintype "passive"))
    )
    (net (code "31") (name "/PASSIVE3_CLK_N") (class "Default")
      (node (ref "R61") (pin "1") (pinfunction "1_1") (pintype "passive"))
      (node (ref "TR2") (pin "6") (pinfunction "BAL_P1_6") (pintype "passive"))
    )
    (net (code "32") (name "/PASSIVE3_CLK_P") (class "Default")
      (node (ref "R60") (pin "1") (pinfunction "1_1") (pintype "passive"))
      (node (ref "TR2") (pin "8") (pinfunction "BAL_P2_8") (pintype "passive"))
    )
    (net (code "33") (name "/PASSIVE4_CLK_N") (class "Default")
      (node (ref "R59") (pin "1") (pinfunction "1_1") (pintype "passive"))
      (node (ref "TR5") (pin "6") (pinfunction "BAL_P1_6") (pintype "passive"))
    )
    (net (code "34") (name "/PASSIVE4_CLK_P") (class "Default")
      (node (ref "R58") (pin "1") (pinfunction "1_1") (pintype "passive"))
      (node (ref "TR5") (pin "8") (pinfunction "BAL_P2_8") (pintype "passive"))
    )
    (net (code "35") (name "/REFIN_C_N") (class "Default")
      (node (ref "C49") (pin "1") (pinfunction "1_1") (pintype "passive"))
      (node (ref "IC3") (pin "2") (pinfunction "REFINB_2") (pintype "input"))
    )
    (net (code "36") (name "/REFIN_C_P") (class "Default")
      (node (ref "C47") (pin "1") (pinfunction "1_1") (pintype "passive"))
      (node (ref "IC3") (pin "1") (pinfunction "REFIN_1") (pintype "input"))
    )
    (net (code "37") (name "/REFIN_N") (class "Default")
      (node (ref "C49") (pin "2") (pinfunction "2_2") (pintype "passive"))
      (node (ref "IC16") (pin "8") (pinfunction "D+_8") (pintype "bidirectional"))
    )
    (net (code "38") (name "/REFIN_P") (class "Default")
      (node (ref "C47") (pin "2") (pinfunction "2_2") (pintype "passive"))
      (node (ref "IC16") (pin "7") (pinfunction "D-_7") (pintype "bidirectional"))
    )
    (net (code "39") (name "/REF_CLK_SEL") (class "Default")
      (node (ref "IC16") (pin "9") (pinfunction "S_9") (pintype "input"))
      (node (ref "R48") (pin "2") (pinfunction "2_2") (pintype "passive"))
    )
    (net (code "40") (name "/RF1") (class "Default")
      (node (ref "C40") (pin "2") (pinfunction "2_2") (pintype "passive"))
      (node (ref "C42") (pin "2") (pinfunction "2_2") (pintype "passive"))
      (node (ref "J2") (pin "1") (pinfunction "1_1") (pintype "bidirectional"))
    )
    (net (code "41") (name "/RF2") (class "Default")
      (node (ref "C48") (pin "2") (pinfunction "2_2") (pintype "passive"))
      (node (ref "J10") (pin "1") (pinfunction "1_1") (pintype "bidirectional"))
    )
    (net (code "42") (name "/RF4") (class "Default")
      (node (ref "IC4") (pin "10") (pinfunction "PORT_4_10") (pintype "input"))
      (node (ref "TR3") (pin "1") (pinfunction "UNBAL_1") (pintype "passive"))
    )
    (net (code "43") (name "/RF5") (class "Default")
      (node (ref "IC4") (pin "9") (pinfunction "PORT_3_9") (pintype "input"))
      (node (ref "TR4") (pin "1") (pinfunction "UNBAL_1") (pintype "passive"))
    )
    (net (code "44") (name "/RF6") (class "Default")
      (node (ref "IC4") (pin "6") (pinfunction "PORT_1_6") (pintype "input"))
      (node (ref "TR2") (pin "1") (pinfunction "UNBAL_1") (pintype "passive"))
    )
    (net (code "45") (name "/RF7") (class "Default")
      (node (ref "IC4") (pin "7") (pinfunction "PORT_2_7") (pintype "input"))
      (node (ref "TR5") (pin "1") (pinfunction "UNBAL_1") (pintype "passive"))
    )
    (net (code "46") (name "/RF_aux_N") (class "Default")
      (node (ref "IC3") (pin "46") (pinfunction "OUT4B_46") (pintype "output"))
      (node (ref "J4") (pin "1") (pinfunction "1_1") (pintype "bidirectional"))
    )
    (net (code "47") (name "/RF_aux_P") (class "Default")
      (node (ref "IC3") (pin "47") (pinfunction "OUT4_47") (pintype "output"))
      (node (ref "J3") (pin "1") (pinfunction "1_1") (pintype "bidirectional"))
    )
    (net (code "48") (name "/Ref_N") (class "Default")
      (node (ref "IC16") (pin "1") (pinfunction "1D+_1") (pintype "bidirectional"))
      (node (ref "R20") (pin "1") (pinfunction "1_1") (pintype "passive"))
      (node (ref "TR6") (pin "3") (pinfunction "S_3") (pintype "passive"))
    )
    (net (code "49") (name "/Ref_P") (class "Default")
      (node (ref "IC16") (pin "2") (pinfunction "1D-_2") (pintype "bidirectional"))
      (node (ref "R20") (pin "2") (pinfunction "2_2") (pintype "passive"))
      (node (ref "TR6") (pin "1") (pinfunction "SDOT_1") (pintype "passive"))
    )
    (net (code "50") (name "/SCB") (class "Default")
      (node (ref "IC3") (pin "21") (pinfunction "CSB_21") (pintype "input"))
    )
    (net (code "51") (name "/SCLK") (class "Default")
      (node (ref "IC3") (pin "18") (pinfunction "SCLK_18") (pintype "input"))
    )
    (net (code "52") (name "/SDIO") (class "Default")
      (node (ref "IC3") (pin "19") (pinfunction "SDIO_19") (pintype "bidirectional"))
    )
    (net (code "53") (name "/SDO") (class "Default")
      (node (ref "R7") (pin "1") (pinfunction "1_1") (pintype "passive"))
    )
    (net (code "54") (name "/STATUS") (class "Default")
      (node (ref "R19") (pin "1") (pinfunction "1_1") (pintype "passive"))
    )
    (net (code "55") (name "/Si_OE") (class "Default")
      (node (ref "OSC2") (pin "2") (pinfunction "OE_2") (pintype "input"))
    )
    (net (code "56") (name "/Si_SCL") (class "Default")
      (node (ref "OSC2") (pin "8") (pinfunction "SCL_8") (pintype "input"))
      (node (ref "R50") (pin "1") (pinfunction "1_1") (pintype "passive"))
    )
    (net (code "57") (name "/Si_SDA") (class "Default")
      (node (ref "OSC2") (pin "7") (pinfunction "SDA_7") (pintype "bidirectional"))
      (node (ref "R49") (pin "1") (pinfunction "1_1") (pintype "passive"))
    )
    (net (code "58") (name "/VCXO_OUT_N") (class "Default")
      (node (ref "C46") (pin "2") (pinfunction "2_2") (pintype "passive"))
      (node (ref "R52") (pin "1") (pinfunction "1_1") (pintype "passive"))
      (node (ref "R73") (pin "2") (pinfunction "2_2") (pintype "passive"))
    )
    (net (code "59") (name "/VCXO_OUT_P") (class "Default")
      (node (ref "C45") (pin "2") (pinfunction "2_2") (pintype "passive"))
      (node (ref "R30") (pin "1") (pinfunction "1_1") (pintype "passive"))
      (node (ref "R51") (pin "2") (pinfunction "2_2") (pintype "passive"))
      (node (ref "R72") (pin "2") (pinfunction "2_2") (pintype "passive"))
    )
    (net (code "60") (name "GND") (class "Default")
      (node (ref "C10") (pin "2") (pinfunction "2_2") (pintype "passive"))
      (node (ref "C105") (pin "1") (pinfunction "1_1") (pintype "passive"))
      (node (ref "C106") (pin "1") (pinfunction "1_1") (pintype "passive"))
      (node (ref "C107") (pin "1") (pinfunction "1_1") (pintype "passive"))
      (node (ref "C108") (pin "1") (pinfunction "1_1") (pintype "passive"))
      (node (ref "C109") (pin "1") (pinfunction "1_1") (pintype "passive"))
      (node (ref "C110") (pin "1") (pinfunction "1_1") (pintype "passive"))
      (node (ref "C50") (pin "2") (pinfunction "2_2") (pintype "passive"))
      (node (ref "C53") (pin "1") (pinfunction "1_1") (pintype "passive"))
      (node (ref "C54") (pin "2") (pinfunction "2_2") (pintype "passive"))
      (node (ref "C55") (pin "1") (pinfunction "1_1") (pintype "passive"))
      (node (ref "C56") (pin "1") (pinfunction "1_1") (pintype "passive"))
      (node (ref "C57") (pin "1") (pinfunction "1_1") (pintype "passive"))
      (node (ref "C58") (pin "1") (pinfunction "1_1") (pintype "passive"))
      (node (ref "C59") (pin "1") (pinfunction "1_1") (pintype "passive"))
      (node (ref "C60") (pin "1") (pinfunction "1_1") (pintype "passive"))
      (node (ref "C61") (pin "1") (pinfunction "1_1") (pintype "passive"))
      (node (ref "C62") (pin "1") (pinfunction "1_1") (pintype "passive"))
      (node (ref "C63") (pin "1") (pinfunction "1_1") (pintype "passive"))
      (node (ref "C64") (pin "1") (pinfunction "1_1") (pintype "passive"))
      (node (ref "C65") (pin "1") (pinfunction "1_1") (pintype "passive"))
      (node (ref "C66") (pin "1") (pinfunction "1_1") (pintype "passive"))
      (node (ref "C67") (pin "1") (pinfunction "1_1") (pintype "passive"))
      (node (ref "C68") (pin "1") (pinfunction "1_1") (pintype "passive"))
      (node (ref "C69") (pin "1") (pinfunction "1_1") (pintype "passive"))
      (node (ref "C70") (pin "1") (pinfunction "1_1") (pintype "passive"))
      (node (ref "C71") (pin "1") (pinfunction "1_1") (pintype "passive"))
      (node (ref "C72") (pin "1") (pinfunction "1_1") (pintype "passive"))
      (node (ref "IC16") (pin "11") (pinfunction "EP_11") (pintype "passive"))
      (node (ref "IC16") (pin "5") (pinfunction "GND_5") (pintype "power_in"))
      (node (ref "IC16") (pin "6") (pinfunction "~{OE}_6") (pintype "input"))
      (node (ref "IC3") (pin "12") (pinfunction "GND_12") (pintype "power_in"))
      (node (ref "IC3") (pin "22") (pinfunction "GND_22") (pintype "power_in"))
      (node (ref "IC3") (pin "27") (pinfunction "GND_27") (pintype "power_in"))
      (node (ref "IC3") (pin "3") (pinfunction "GND_3") (pintype "power_in"))
      (node (ref "IC3") (pin "32") (pinfunction "GND_32") (pintype "power_in"))
      (node (ref "IC3") (pin "49") (pinfunction "GND_49") (pintype "power_in"))
      (node (ref "IC3") (pin "50") (pinfunction "GND_50") (pintype "power_in"))
      (node (ref "IC3") (pin "55") (pinfunction "GND_55") (pintype "power_in"))
      (node (ref "IC3") (pin "62") (pinfunction "GND_62") (pintype "power_in"))
      (node (ref "IC3") (pin "65") (pinfunction "EP_65") (pintype "power_in"))
      (node (ref "IC3") (pin "7") (pinfunction "GND_7") (pintype "power_in"))
      (node (ref "IC3") (pin "8") (pinfunction "GND_8") (pintype "power_in"))
      (node (ref "IC4") (pin "1") (pinfunction "GND_1") (pintype "power_in"))
      (node (ref "IC4") (pin "2") (pinfunction "GND_2") (pintype "power_in"))
      (node (ref "IC4") (pin "4") (pinfunction "GND_4") (pintype "power_in"))
      (node (ref "IC4") (pin "5") (pinfunction "GND_5") (pintype "power_in"))
      (node (ref "IC4") (pin "8") (pinfunction "GND_8") (pintype "power_in"))
      (node (ref "J3") (pin "2") (pinfunction "2_2") (pintype "bidirectional"))
      (node (ref "J4") (pin "2") (pinfunction "2_2") (pintype "bidirectional"))
      (node (ref "OSC1") (pin "2") (pinfunction "GND_2") (pintype "power_in"))
      (node (ref "OSC2") (pin "3") (pinfunction "GND_3") (pintype "power_in"))
      (node (ref "R21") (pin "2") (pinfunction "2_2") (pintype "passive"))
      (node (ref "R24") (pin "1") (pinfunction "1_1") (pintype "passive"))
      (node (ref "R25") (pin "2") (pinfunction "2_2") (pintype "passive"))
      (node (ref "R26") (pin "2") (pinfunction "2_2") (pintype "passive"))
      (node (ref "R29") (pin "2") (pinfunction "2_2") (pintype "passive"))
      (node (ref "R30") (pin "2") (pinfunction "2_2") (pintype "passive"))
      (node (ref "R31") (pin "2") (pinfunction "2_2") (pintype "passive"))
      (node (ref "R34") (pin "2") (pinfunction "2_2") (pintype "passive"))
      (node (ref "R36") (pin "2") (pinfunction "2_2") (pintype "passive"))
      (node (ref "R38") (pin "2") (pinfunction "2_2") (pintype "passive"))
      (node (ref "R40") (pin "1") (pinfunction "1_1") (pintype "passive"))
      (node (ref "R46") (pin "1") (pinfunction "1_1") (pintype "passive"))
      (node (ref "R47") (pin "1") (pinfunction "1_1") (pintype "passive"))
      (node (ref "R48") (pin "1") (pinfunction "1_1") (pintype "passive"))
      (node (ref "R52") (pin "2") (pinfunction "2_2") (pintype "passive"))
      (node (ref "TR2") (pin "10") (pinfunction "GND_10") (pintype "power_in"))
      (node (ref "TR2") (pin "3") (pinfunction "GND_3") (pintype "power_in"))
      (node (ref "TR2") (pin "4") (pinfunction "GND_4") (pintype "power_in"))
      (node (ref "TR2") (pin "5") (pinfunction "GND_5") (pintype "power_in"))
      (node (ref "TR2") (pin "9") (pinfunction "GND_9") (pintype "power_in"))
      (node (ref "TR3") (pin "10") (pinfunction "GND_10") (pintype "power_in"))
      (node (ref "TR3") (pin "3") (pinfunction "GND_3") (pintype "power_in"))
      (node (ref "TR3") (pin "4") (pinfunction "GND_4") (pintype "power_in"))
      (node (ref "TR3") (pin "5") (pinfunction "GND_5") (pintype "power_in"))
      (node (ref "TR3") (pin "9") (pinfunction "GND_9") (pintype "power_in"))
      (node (ref "TR4") (pin "10") (pinfunction "GND_10") (pintype "power_in"))
      (node (ref "TR4") (pin "3") (pinfunction "GND_3") (pintype "power_in"))
      (node (ref "TR4") (pin "4") (pinfunction "GND_4") (pintype "power_in"))
      (node (ref "TR4") (pin "5") (pinfunction "GND_5") (pintype "power_in"))
      (node (ref "TR4") (pin "9") (pinfunction "GND_9") (pintype "power_in"))
      (node (ref "TR5") (pin "10") (pinfunction "GND_10") (pintype "power_in"))
      (node (ref "TR5") (pin "3") (pinfunction "GND_3") (pintype "power_in"))
      (node (ref "TR5") (pin "4") (pinfunction "GND_4") (pintype "power_in"))
      (node (ref "TR5") (pin "5") (pinfunction "GND_5") (pintype "power_in"))
      (node (ref "TR5") (pin "9") (pinfunction "GND_9") (pintype "power_in"))
    )
    (net (code "61") (name "Net-(C42-Pad1)") (class "Default")
      (node (ref "C42") (pin "1") (pinfunction "1_1") (pintype "passive"))
      (node (ref "L5") (pin "5") (pinfunction "5_5") (pintype "passive"))
    )
    (net (code "62") (name "Net-(C43-Pad1)") (class "Default")
      (node (ref "C43") (pin "1") (pinfunction "1_1") (pintype "passive"))
      (node (ref "L5") (pin "4") (pinfunction "4_4") (pintype "passive"))
    )
    (net (code "63") (name "Net-(C56-Pad2)") (class "Default")
      (node (ref "C56") (pin "2") (pinfunction "2_2") (pintype "passive"))
      (node (ref "R53") (pin "2") (pinfunction "2_2") (pintype "passive"))
      (node (ref "R54") (pin "1") (pinfunction "1_1") (pintype "passive"))
    )
    (net (code "64") (name "Net-(C58-Pad2)") (class "Default")
      (node (ref "C58") (pin "2") (pinfunction "2_2") (pintype "passive"))
      (node (ref "R55") (pin "1") (pinfunction "1_1") (pintype "passive"))
    )
    (net (code "65") (name "Net-(IC3-CLK2)") (class "Default")
      (node (ref "C45") (pin "1") (pinfunction "1_1") (pintype "passive"))
      (node (ref "IC3") (pin "10") (pinfunction "CLK2_10") (pintype "input"))
    )
    (net (code "66") (name "Net-(IC3-CLK2B)") (class "Default")
      (node (ref "C46") (pin "1") (pinfunction "1_1") (pintype "passive"))
      (node (ref "IC3") (pin "11") (pinfunction "CLK2B_11") (pintype "input"))
    )
    (net (code "67") (name "Net-(IC3-CP)") (class "Default")
      (node (ref "C55") (pin "2") (pinfunction "2_2") (pintype "passive"))
      (node (ref "IC3") (pin "6") (pinfunction "CP_6") (pintype "output"))
      (node (ref "R53") (pin "1") (pinfunction "1_1") (pintype "passive"))
      (node (ref "R55") (pin "2") (pinfunction "2_2") (pintype "passive"))
    )
    (net (code "68") (name "Net-(IC3-CPRSET)") (class "Default")
      (node (ref "IC3") (pin "63") (pinfunction "CPRSET_63") (pintype "input"))
      (node (ref "R46") (pin "2") (pinfunction "2_2") (pintype "passive"))
    )
    (net (code "69") (name "Net-(IC3-RSET)") (class "Default")
      (node (ref "IC3") (pin "61") (pinfunction "RSET_61") (pintype "input"))
      (node (ref "R47") (pin "2") (pinfunction "2_2") (pintype "passive"))
    )
    (net (code "70") (name "Net-(IC3-SDO)") (class "Default")
      (node (ref "IC3") (pin "20") (pinfunction "SDO_20") (pintype "output"))
      (node (ref "R7") (pin "2") (pinfunction "2_2") (pintype "passive"))
    )
    (net (code "71") (name "Net-(IC3-STATUS)") (class "Default")
      (node (ref "IC3") (pin "17") (pinfunction "STATUS_17") (pintype "output"))
      (node (ref "R19") (pin "2") (pinfunction "2_2") (pintype "passive"))
    )
    (net (code "72") (name "Net-(OSC1-OUT)") (class "Default")
      (node (ref "OSC1") (pin "3") (pinfunction "OUT_3") (pintype "output"))
      (node (ref "R51") (pin "1") (pinfunction "1_1") (pintype "passive"))
    )
    (net (code "73") (name "Net-(OSC1-VDD)") (class "Default")
      (node (ref "C10") (pin "1") (pinfunction "1_1") (pintype "passive"))
      (node (ref "C53") (pin "2") (pinfunction "2_2") (pintype "passive"))
      (node (ref "C54") (pin "1") (pinfunction "1_1") (pintype "passive"))
      (node (ref "L8") (pin "2") (pinfunction "2_2") (pintype "passive"))
      (node (ref "OSC1") (pin "4") (pinfunction "VDD_4") (pintype "power_in"))
      (node (ref "OSC2") (pin "6") (pinfunction "VDD_6") (pintype "power_in"))
    )
    (net (code "74") (name "Net-(OSC2-CLK+)") (class "Default")
      (node (ref "OSC2") (pin "4") (pinfunction "CLK+_4") (pintype "output"))
      (node (ref "R72") (pin "1") (pinfunction "1_1") (pintype "passive"))
    )
    (net (code "75") (name "Net-(OSC2-CLK-)") (class "Default")
      (node (ref "OSC2") (pin "5") (pinfunction "CLK-_5") (pintype "output"))
      (node (ref "R73") (pin "1") (pinfunction "1_1") (pintype "passive"))
    )
    (net (code "76") (name "Net-(TR6-P)") (class "Default")
      (node (ref "J10") (pin "2") (pinfunction "2_2") (pintype "bidirectional"))
      (node (ref "R40") (pin "2") (pinfunction "2_2") (pintype "passive"))
      (node (ref "TR6") (pin "4") (pinfunction "P_4") (pintype "passive"))
    )
    (net (code "77") (name "Net-(TR6-PDOT)") (class "Default")
      (node (ref "C48") (pin "1") (pinfunction "1_1") (pintype "passive"))
      (node (ref "TR6") (pin "6") (pinfunction "PDOT_6") (pintype "passive"))
    )
    (net (code "78") (name "P3V3_CLK") (class "Default")
      (node (ref "C105") (pin "2") (pinfunction "2_2") (pintype "passive"))
      (node (ref "C106") (pin "2") (pinfunction "2_2") (pintype "passive"))
      (node (ref "C107") (pin "2") (pinfunction "2_2") (pintype "passive"))
      (node (ref "C108") (pin "2") (pinfunction "2_2") (pintype "passive"))
      (node (ref "C109") (pin "2") (pinfunction "2_2") (pintype "passive"))
      (node (ref "C110") (pin "2") (pinfunction "2_2") (pintype "passive"))
      (node (ref "C50") (pin "1") (pinfunction "1_1") (pintype "passive"))
      (node (ref "C59") (pin "2") (pinfunction "2_2") (pintype "passive"))
      (node (ref "C60") (pin "2") (pinfunction "2_2") (pintype "passive"))
      (node (ref "C61") (pin "2") (pinfunction "2_2") (pintype "passive"))
      (node (ref "C62") (pin "2") (pinfunction "2_2") (pintype "passive"))
      (node (ref "C63") (pin "2") (pinfunction "2_2") (pintype "passive"))
      (node (ref "C64") (pin "2") (pinfunction "2_2") (pintype "passive"))
      (node (ref "C65") (pin "2") (pinfunction "2_2") (pintype "passive"))
      (node (ref "C66") (pin "2") (pinfunction "2_2") (pintype "passive"))
      (node (ref "C67") (pin "2") (pinfunction "2_2") (pintype "passive"))
      (node (ref "C68") (pin "2") (pinfunction "2_2") (pintype "passive"))
      (node (ref "C69") (pin "2") (pinfunction "2_2") (pintype "passive"))
      (node (ref "C70") (pin "2") (pinfunction "2_2") (pintype "passive"))
      (node (ref "C71") (pin "2") (pinfunction "2_2") (pintype "passive"))
      (node (ref "C72") (pin "2") (pinfunction "2_2") (pintype "passive"))
      (node (ref "IC16") (pin "10") (pinfunction "VCC_10") (pintype "power_in"))
      (node (ref "IC3") (pin "13") (pinfunction "VS_13") (pintype "power_in"))
      (node (ref "IC3") (pin "23") (pinfunction "VS_23") (pintype "power_in"))
      (node (ref "IC3") (pin "26") (pinfunction "VS_26") (pintype "power_in"))
      (node (ref "IC3") (pin "30") (pinfunction "VS_30") (pintype "power_in"))
      (node (ref "IC3") (pin "31") (pinfunction "VS_31") (pintype "power_in"))
      (node (ref "IC3") (pin "33") (pinfunction "VS_33") (pintype "power_in"))
      (node (ref "IC3") (pin "36") (pinfunction "VS_36") (pintype "power_in"))
      (node (ref "IC3") (pin "37") (pinfunction "VS_37") (pintype "power_in"))
      (node (ref "IC3") (pin "4") (pinfunction "VS_4") (pintype "power_in"))
      (node (ref "IC3") (pin "40") (pinfunction "VS_40") (pintype "power_in"))
      (node (ref "IC3") (pin "41") (pinfunction "VS_41") (pintype "power_in"))
      (node (ref "IC3") (pin "44") (pinfunction "VS_44") (pintype "power_in"))
      (node (ref "IC3") (pin "45") (pinfunction "VS_45") (pintype "power_in"))
      (node (ref "IC3") (pin "48") (pinfunction "VS_48") (pintype "power_in"))
      (node (ref "IC3") (pin "5") (pinfunction "VCP_5") (pintype "power_in"))
      (node (ref "IC3") (pin "51") (pinfunction "VS_51") (pintype "power_in"))
      (node (ref "IC3") (pin "52") (pinfunction "VS_52") (pintype "power_in"))
      (node (ref "IC3") (pin "56") (pinfunction "VS_56") (pintype "power_in"))
      (node (ref "IC3") (pin "59") (pinfunction "VS_59") (pintype "power_in"))
      (node (ref "IC3") (pin "60") (pinfunction "VS_60") (pintype "power_in"))
      (node (ref "IC3") (pin "64") (pinfunction "VS_64") (pintype "power_in"))
      (node (ref "IC3") (pin "9") (pinfunction "VS_9") (pintype "power_in"))
      (node (ref "L8") (pin "1") (pinfunction "1_1") (pintype "passive"))
      (node (ref "R49") (pin "2") (pinfunction "2_2") (pintype "passive"))
      (node (ref "R50") (pin "2") (pinfunction "2_2") (pintype "passive"))
    )
    (net (code "79") (name "unconnected-(IC3-OUT5-Pad43)") (class "Default")
      (node (ref "IC3") (pin "43") (pinfunction "OUT5_43") (pintype "output"))
    )
    (net (code "80") (name "unconnected-(IC3-OUT5B-Pad42)") (class "Default")
      (node (ref "IC3") (pin "42") (pinfunction "OUT5B_42") (pintype "output"))
    )
    (net (code "81") (name "unconnected-(IC3-OUT6-Pad39)") (class "Default")
      (node (ref "IC3") (pin "39") (pinfunction "OUT6_39") (pintype "output"))
    )
    (net (code "82") (name "unconnected-(IC3-OUT6B-Pad38)") (class "Default")
      (node (ref "IC3") (pin "38") (pinfunction "OUT6B_38") (pintype "output"))
    )
    (net (code "83") (name "unconnected-(TR2-OPEN-Pad2)") (class "Default")
      (node (ref "TR2") (pin "2") (pinfunction "OPEN_2") (pintype "passive"))
    )
    (net (code "84") (name "unconnected-(TR2-OPEN-Pad7)") (class "Default")
      (node (ref "TR2") (pin "7") (pinfunction "OPEN_7") (pintype "passive"))
    )
    (net (code "85") (name "unconnected-(TR3-OPEN-Pad2)") (class "Default")
      (node (ref "TR3") (pin "2") (pinfunction "OPEN_2") (pintype "passive"))
    )
    (net (code "86") (name "unconnected-(TR3-OPEN-Pad7)") (class "Default")
      (node (ref "TR3") (pin "7") (pinfunction "OPEN_7") (pintype "passive"))
    )
    (net (code "87") (name "unconnected-(TR4-OPEN-Pad2)") (class "Default")
      (node (ref "TR4") (pin "2") (pinfunction "OPEN_2") (pintype "passive"))
    )
    (net (code "88") (name "unconnected-(TR4-OPEN-Pad7)") (class "Default")
      (node (ref "TR4") (pin "7") (pinfunction "OPEN_7") (pintype "passive"))
    )
    (net (code "89") (name "unconnected-(TR5-OPEN-Pad2)") (class "Default")
      (node (ref "TR5") (pin "2") (pinfunction "OPEN_2") (pintype "passive"))
    )
    (net (code "90") (name "unconnected-(TR5-OPEN-Pad7)") (class "Default")
      (node (ref "TR5") (pin "7") (pinfunction "OPEN_7") (pintype "passive"))
    )
    (net (code "91") (name "unconnected-(TR6-NU-Pad2)") (class "Default")
      (node (ref "TR6") (pin "2") (pinfunction "NU_2") (pintype "passive"))
    )
  )
)
